# PLT-01-RevEe.net
KiCad netlist of a schematic drawn in EAGLE
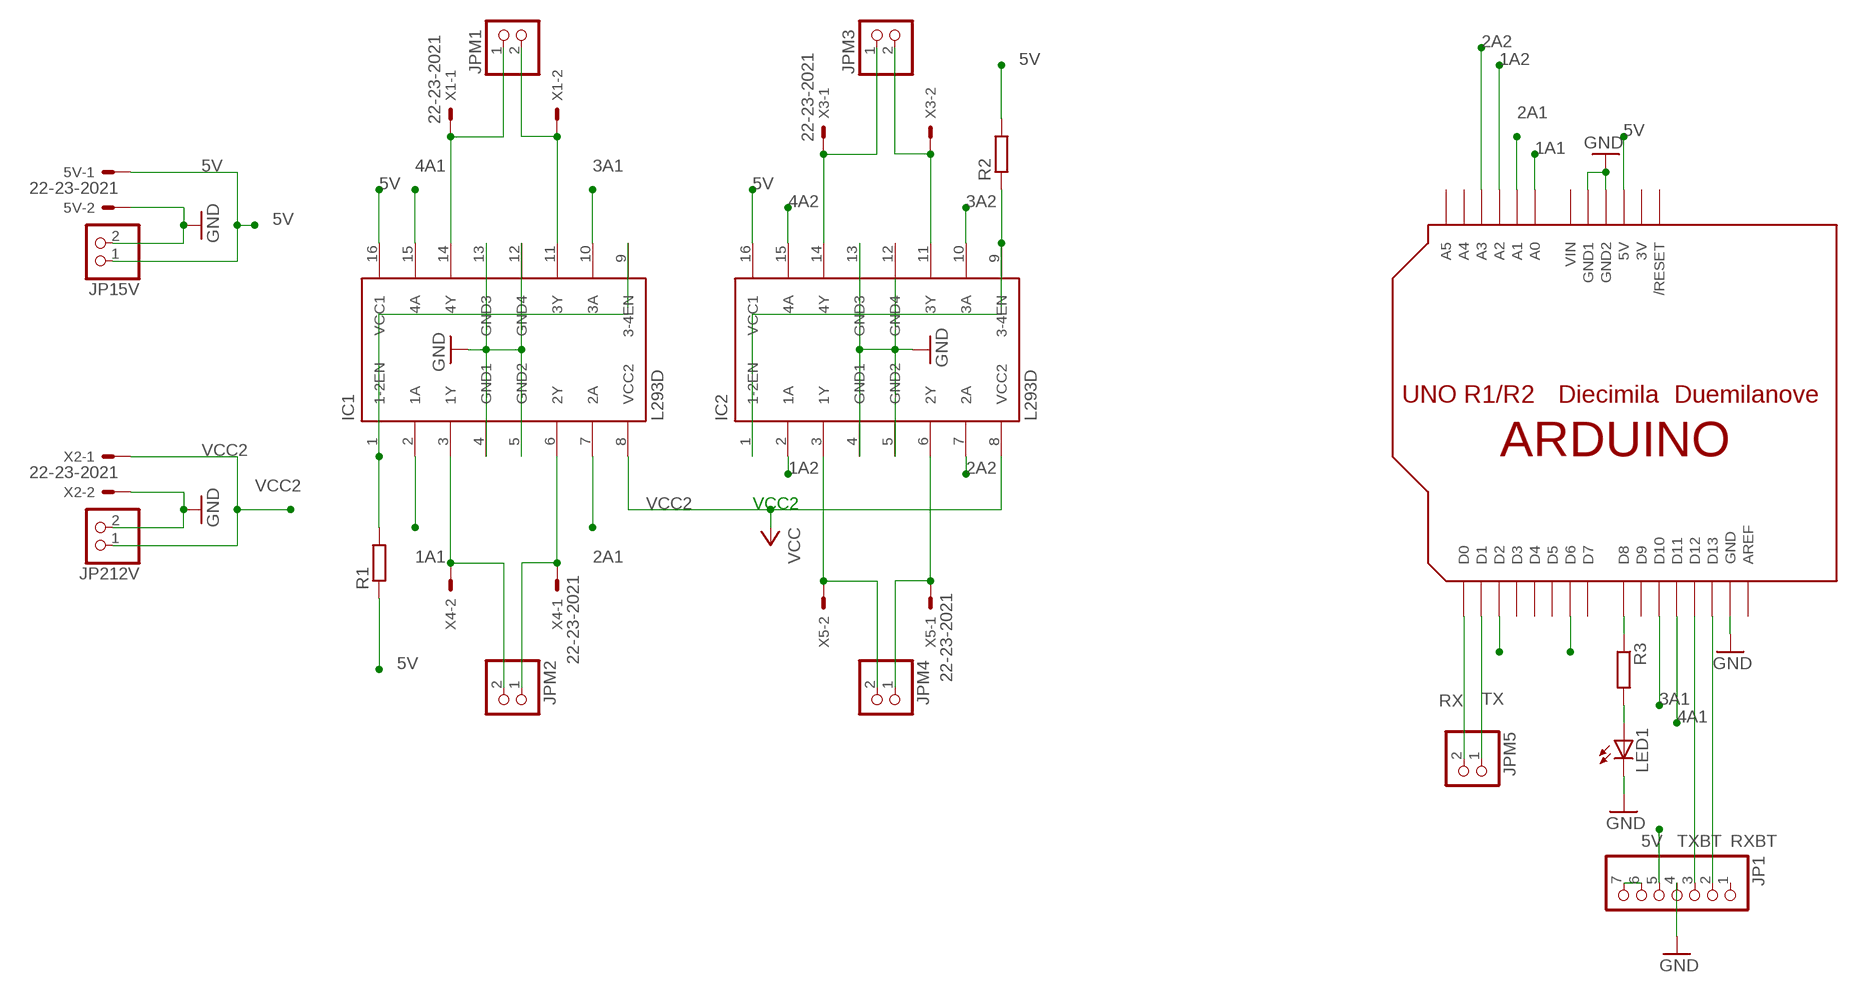
[diagram p0: schematic, sheet 1]

(export (version "E")
  (design (tool "Eeschema 10.0.6"))
  (components
    (comp (ref "5V")
      (value "22-23-2021")
      (footprint "eagle-import:22-23-2021")
      (fields (field (name "MF") "MOLEX"))
      (libsource (lib "eagle-import") (part "22-23-2021"))
    )
    (comp (ref "IC1")
      (value "L293D")
      (footprint "eagle-import:DIL16")
      (libsource (lib "eagle-import") (part "L293D"))
    )
    (comp (ref "IC2")
      (value "L293D")
      (footprint "eagle-import:DIL16")
      (libsource (lib "eagle-import") (part "L293D"))
    )
    (comp (ref "JP1")
      (value "PINHD-1X7")
      (footprint "eagle-import:1X07")
      (libsource (lib "eagle-import") (part "PINHD-1X7"))
    )
    (comp (ref "JP15V")
      (value "PINHD-1X2")
      (footprint "eagle-import:1X02")
      (libsource (lib "eagle-import") (part "PINHD-1X2"))
    )
    (comp (ref "JP212V")
      (value "PINHD-1X2")
      (footprint "eagle-import:1X02")
      (libsource (lib "eagle-import") (part "PINHD-1X2"))
    )
    (comp (ref "JPM1")
      (value "PINHD-1X2")
      (footprint "eagle-import:1X02")
      (libsource (lib "eagle-import") (part "PINHD-1X2"))
    )
    (comp (ref "JPM2")
      (value "PINHD-1X2")
      (footprint "eagle-import:1X02")
      (libsource (lib "eagle-import") (part "PINHD-1X2"))
    )
    (comp (ref "JPM3")
      (value "PINHD-1X2")
      (footprint "eagle-import:1X02")
      (libsource (lib "eagle-import") (part "PINHD-1X2"))
    )
    (comp (ref "JPM4")
      (value "PINHD-1X2")
      (footprint "eagle-import:1X02")
      (libsource (lib "eagle-import") (part "PINHD-1X2"))
    )
    (comp (ref "JPM5")
      (value "PINHD-1X2")
      (footprint "eagle-import:1X02")
      (libsource (lib "eagle-import") (part "PINHD-1X2"))
    )
    (comp (ref "LED1")
      (value "LED5MM")
      (footprint "eagle-import:LED5MM")
      (libsource (lib "eagle-import") (part "LED5MM"))
    )
    (comp (ref "R1")
      (value "R-EU_0207/10")
      (footprint "eagle-import:0207_10")
      (libsource (lib "eagle-import") (part "R-EU_0207/10"))
    )
    (comp (ref "R2")
      (value "R-EU_0207/10")
      (footprint "eagle-import:0207_10")
      (libsource (lib "eagle-import") (part "R-EU_0207/10"))
    )
    (comp (ref "R3")
      (value "R-EU_0207/10")
      (footprint "eagle-import:0207_10")
      (libsource (lib "eagle-import") (part "R-EU_0207/10"))
    )
    (comp (ref "U$1")
      (value "ARDUINOUNO")
      (footprint "eagle-import:ARDUINO")
      (libsource (lib "eagle-import") (part "ARDUINOUNO"))
    )
    (comp (ref "X1")
      (value "22-23-2021")
      (footprint "eagle-import:22-23-2021")
      (fields (field (name "MF") "MOLEX"))
      (libsource (lib "eagle-import") (part "22-23-2021"))
    )
    (comp (ref "X2")
      (value "22-23-2021")
      (footprint "eagle-import:22-23-2021")
      (fields (field (name "MF") "MOLEX"))
      (libsource (lib "eagle-import") (part "22-23-2021"))
    )
    (comp (ref "X3")
      (value "22-23-2021")
      (footprint "eagle-import:22-23-2021")
      (fields (field (name "MF") "MOLEX"))
      (libsource (lib "eagle-import") (part "22-23-2021"))
    )
    (comp (ref "X4")
      (value "22-23-2021")
      (footprint "eagle-import:22-23-2021")
      (fields (field (name "MF") "MOLEX"))
      (libsource (lib "eagle-import") (part "22-23-2021"))
    )
    (comp (ref "X5")
      (value "22-23-2021")
      (footprint "eagle-import:22-23-2021")
      (fields (field (name "MF") "MOLEX"))
      (libsource (lib "eagle-import") (part "22-23-2021"))
    )
  )
  (nets
    (net (code "1") (name "/1A1") (class "Default")
      (node (ref "IC1") (pin "2") (pinfunction "1A_2") (pintype "input"))
      (node (ref "U$1") (pin "A0") (pinfunction "A0_A0") (pintype "bidirectional"))
    )
    (net (code "2") (name "/1A2") (class "Default")
      (node (ref "IC2") (pin "2") (pinfunction "1A_2") (pintype "input"))
      (node (ref "U$1") (pin "A2") (pinfunction "A2_A2") (pintype "bidirectional"))
    )
    (net (code "3") (name "/2A1") (class "Default")
      (node (ref "IC1") (pin "7") (pinfunction "2A_7") (pintype "input"))
      (node (ref "U$1") (pin "A1") (pinfunction "A1_A1") (pintype "bidirectional"))
    )
    (net (code "4") (name "/2A2") (class "Default")
      (node (ref "IC2") (pin "7") (pinfunction "2A_7") (pintype "input"))
      (node (ref "U$1") (pin "A3") (pinfunction "A3_A3") (pintype "bidirectional"))
    )
    (net (code "5") (name "/3A1") (class "Default")
      (node (ref "IC1") (pin "10") (pinfunction "3A_10") (pintype "input"))
      (node (ref "U$1") (pin "D10") (pinfunction "D10_D10") (pintype "bidirectional"))
    )
    (net (code "6") (name "/3A2") (class "Default")
      (node (ref "IC2") (pin "10") (pinfunction "3A_10") (pintype "input"))
      (node (ref "U$1") (pin "D2") (pinfunction "D2_D2") (pintype "bidirectional"))
    )
    (net (code "7") (name "/3V") (class "Default")
      (node (ref "U$1") (pin "3V") (pinfunction "3V_3V") (pintype "power_in"))
    )
    (net (code "8") (name "/4A1") (class "Default")
      (node (ref "IC1") (pin "15") (pinfunction "4A_15") (pintype "input"))
      (node (ref "U$1") (pin "D11") (pinfunction "D11_D11") (pintype "bidirectional"))
    )
    (net (code "9") (name "/4A2") (class "Default")
      (node (ref "IC2") (pin "15") (pinfunction "4A_15") (pintype "input"))
      (node (ref "U$1") (pin "D6") (pinfunction "D6_D6") (pintype "bidirectional"))
    )
    (net (code "10") (name "/5V") (class "Default")
      (node (ref "5V") (pin "1") (pinfunction "S_1") (pintype "passive"))
      (node (ref "IC1") (pin "16") (pinfunction "VCC1_16") (pintype "power_in"))
      (node (ref "IC2") (pin "16") (pinfunction "VCC1_16") (pintype "power_in"))
      (node (ref "JP1") (pin "5") (pinfunction "5_5") (pintype "passive"))
      (node (ref "JP15V") (pin "1") (pinfunction "1_1") (pintype "passive"))
      (node (ref "R1") (pin "1") (pinfunction "1_1") (pintype "passive"))
      (node (ref "R2") (pin "2") (pinfunction "2_2") (pintype "passive"))
      (node (ref "U$1") (pin "5V") (pinfunction "5V_5V") (pintype "power_in"))
    )
    (net (code "11") (name "/GND4") (class "Default")
      (node (ref "IC2") (pin "12") (pinfunction "GND4_12") (pintype "power_in"))
    )
    (net (code "12") (name "/RX") (class "Default")
      (node (ref "JPM5") (pin "2") (pinfunction "2_2") (pintype "passive"))
      (node (ref "U$1") (pin "D0") (pinfunction "D0_D0") (pintype "bidirectional"))
    )
    (net (code "13") (name "/RXBT") (class "Default")
      (node (ref "JP1") (pin "2") (pinfunction "2_2") (pintype "passive"))
      (node (ref "U$1") (pin "D13") (pinfunction "D13_D13") (pintype "bidirectional"))
    )
    (net (code "14") (name "/TX") (class "Default")
      (node (ref "JPM5") (pin "1") (pinfunction "1_1") (pintype "passive"))
      (node (ref "U$1") (pin "D1") (pinfunction "D1_D1") (pintype "bidirectional"))
    )
    (net (code "15") (name "/TXBT") (class "Default")
      (node (ref "JP1") (pin "3") (pinfunction "3_3") (pintype "passive"))
      (node (ref "U$1") (pin "D12") (pinfunction "D12_D12") (pintype "bidirectional"))
    )
    (net (code "16") (name "/VIN") (class "Default")
      (node (ref "U$1") (pin "VIN") (pinfunction "VIN_VIN") (pintype "power_in"))
    )
    (net (code "17") (name "GND") (class "Default")
      (node (ref "5V") (pin "2") (pinfunction "S_2") (pintype "passive"))
      (node (ref "IC1") (pin "12") (pinfunction "GND4_12") (pintype "power_in"))
      (node (ref "IC1") (pin "13") (pinfunction "GND3_13") (pintype "power_in"))
      (node (ref "IC1") (pin "4") (pinfunction "GND1_4") (pintype "power_in"))
      (node (ref "IC1") (pin "5") (pinfunction "GND2_5") (pintype "power_in"))
      (node (ref "IC2") (pin "13") (pinfunction "GND3_13") (pintype "power_in"))
      (node (ref "IC2") (pin "4") (pinfunction "GND1_4") (pintype "power_in"))
      (node (ref "IC2") (pin "5") (pinfunction "GND2_5") (pintype "power_in"))
      (node (ref "JP1") (pin "4") (pinfunction "4_4") (pintype "passive"))
      (node (ref "JP15V") (pin "2") (pinfunction "2_2") (pintype "passive"))
      (node (ref "JP212V") (pin "2") (pinfunction "2_2") (pintype "passive"))
      (node (ref "LED1") (pin "K") (pinfunction "C_K") (pintype "passive"))
      (node (ref "U$1") (pin "GND") (pinfunction "GND_GND") (pintype "power_in"))
      (node (ref "U$1") (pin "GND1") (pinfunction "GND1_GND1") (pintype "power_in"))
      (node (ref "U$1") (pin "GND2") (pinfunction "GND2_GND2") (pintype "power_in"))
      (node (ref "X2") (pin "2") (pinfunction "S_2") (pintype "passive"))
    )
    (net (code "18") (name "Net-(IC1-1-2EN)") (class "Default")
      (node (ref "IC1") (pin "1") (pinfunction "1-2EN_1") (pintype "input"))
      (node (ref "IC1") (pin "9") (pinfunction "3-4EN_9") (pintype "input"))
      (node (ref "R1") (pin "2") (pinfunction "2_2") (pintype "passive"))
    )
    (net (code "19") (name "Net-(IC1-1Y)") (class "Default")
      (node (ref "IC1") (pin "3") (pinfunction "1Y_3") (pintype "output"))
      (node (ref "JPM2") (pin "2") (pinfunction "2_2") (pintype "passive"))
      (node (ref "X4") (pin "2") (pinfunction "S_2") (pintype "passive"))
    )
    (net (code "20") (name "Net-(IC1-2Y)") (class "Default")
      (node (ref "IC1") (pin "6") (pinfunction "2Y_6") (pintype "output"))
      (node (ref "JPM2") (pin "1") (pinfunction "1_1") (pintype "passive"))
      (node (ref "X4") (pin "1") (pinfunction "S_1") (pintype "passive"))
    )
    (net (code "21") (name "Net-(IC1-3Y)") (class "Default")
      (node (ref "IC1") (pin "11") (pinfunction "3Y_11") (pintype "output"))
      (node (ref "JPM1") (pin "2") (pinfunction "2_2") (pintype "passive"))
      (node (ref "X1") (pin "2") (pinfunction "S_2") (pintype "passive"))
    )
    (net (code "22") (name "Net-(IC1-4Y)") (class "Default")
      (node (ref "IC1") (pin "14") (pinfunction "4Y_14") (pintype "output"))
      (node (ref "JPM1") (pin "1") (pinfunction "1_1") (pintype "passive"))
      (node (ref "X1") (pin "1") (pinfunction "S_1") (pintype "passive"))
    )
    (net (code "23") (name "Net-(IC2-1-2EN)") (class "Default")
      (node (ref "IC2") (pin "1") (pinfunction "1-2EN_1") (pintype "input"))
      (node (ref "IC2") (pin "9") (pinfunction "3-4EN_9") (pintype "input"))
      (node (ref "R2") (pin "1") (pinfunction "1_1") (pintype "passive"))
    )
    (net (code "24") (name "Net-(IC2-1Y)") (class "Default")
      (node (ref "IC2") (pin "3") (pinfunction "1Y_3") (pintype "output"))
      (node (ref "JPM4") (pin "2") (pinfunction "2_2") (pintype "passive"))
      (node (ref "X5") (pin "2") (pinfunction "S_2") (pintype "passive"))
    )
    (net (code "25") (name "Net-(IC2-2Y)") (class "Default")
      (node (ref "IC2") (pin "6") (pinfunction "2Y_6") (pintype "output"))
      (node (ref "JPM4") (pin "1") (pinfunction "1_1") (pintype "passive"))
      (node (ref "X5") (pin "1") (pinfunction "S_1") (pintype "passive"))
    )
    (net (code "26") (name "Net-(IC2-3Y)") (class "Default")
      (node (ref "IC2") (pin "11") (pinfunction "3Y_11") (pintype "output"))
      (node (ref "JPM3") (pin "2") (pinfunction "2_2") (pintype "passive"))
      (node (ref "X3") (pin "2") (pinfunction "S_2") (pintype "passive"))
    )
    (net (code "27") (name "Net-(IC2-4Y)") (class "Default")
      (node (ref "IC2") (pin "14") (pinfunction "4Y_14") (pintype "output"))
      (node (ref "JPM3") (pin "1") (pinfunction "1_1") (pintype "passive"))
      (node (ref "X3") (pin "1") (pinfunction "S_1") (pintype "passive"))
    )
    (net (code "28") (name "Net-(JP1-Pad6)") (class "Default")
      (node (ref "JP1") (pin "6") (pinfunction "6_6") (pintype "passive"))
      (node (ref "JP1") (pin "7") (pinfunction "7_7") (pintype "passive"))
    )
    (net (code "29") (name "Net-(LED1-PadA)") (class "Default")
      (node (ref "LED1") (pin "A") (pinfunction "A_A") (pintype "passive"))
      (node (ref "R3") (pin "2") (pinfunction "2_2") (pintype "passive"))
    )
    (net (code "30") (name "Net-(R3-Pad1)") (class "Default")
      (node (ref "R3") (pin "1") (pinfunction "1_1") (pintype "passive"))
      (node (ref "U$1") (pin "D8") (pinfunction "D8_D8") (pintype "bidirectional"))
    )
    (net (code "31") (name "VCC") (class "Default")
      (node (ref "IC1") (pin "8") (pinfunction "VCC2_8") (pintype "power_in"))
      (node (ref "IC2") (pin "8") (pinfunction "VCC2_8") (pintype "power_in"))
      (node (ref "JP212V") (pin "1") (pinfunction "1_1") (pintype "passive"))
      (node (ref "X2") (pin "1") (pinfunction "S_1") (pintype "passive"))
    )
    (net (code "32") (name "unconnected-(JP1-Pad1)") (class "Default")
      (node (ref "JP1") (pin "1") (pinfunction "1_1") (pintype "passive"))
    )
    (net (code "33") (name "unconnected-(U$1-PadA4)") (class "Default")
      (node (ref "U$1") (pin "A4") (pinfunction "A4_A4") (pintype "bidirectional"))
    )
    (net (code "34") (name "unconnected-(U$1-PadA5)") (class "Default")
      (node (ref "U$1") (pin "A5") (pinfunction "A5_A5") (pintype "bidirectional"))
    )
    (net (code "35") (name "unconnected-(U$1-PadAREF)") (class "Default")
      (node (ref "U$1") (pin "AREF") (pinfunction "AREF_AREF") (pintype "bidirectional"))
    )
    (net (code "36") (name "unconnected-(U$1-PadD3)") (class "Default")
      (node (ref "U$1") (pin "D3") (pinfunction "D3_D3") (pintype "bidirectional"))
    )
    (net (code "37") (name "unconnected-(U$1-PadD4)") (class "Default")
      (node (ref "U$1") (pin "D4") (pinfunction "D4_D4") (pintype "bidirectional"))
    )
    (net (code "38") (name "unconnected-(U$1-PadD5)") (class "Default")
      (node (ref "U$1") (pin "D5") (pinfunction "D5_D5") (pintype "bidirectional"))
    )
    (net (code "39") (name "unconnected-(U$1-PadD7)") (class "Default")
      (node (ref "U$1") (pin "D7") (pinfunction "D7_D7") (pintype "bidirectional"))
    )
    (net (code "40") (name "unconnected-(U$1-PadD9)") (class "Default")
      (node (ref "U$1") (pin "D9") (pinfunction "D9_D9") (pintype "bidirectional"))
    )
    (net (code "41") (name "unconnected-(U$1-{slash}RESET-PadRESET)") (class "Default")
      (node (ref "U$1") (pin "RESET") (pinfunction "/RESET_RESET") (pintype "bidirectional"))
    )
  )
)
